# DRV8711EVM_FET.net
KiCad netlist of a schematic drawn in Altium Designer
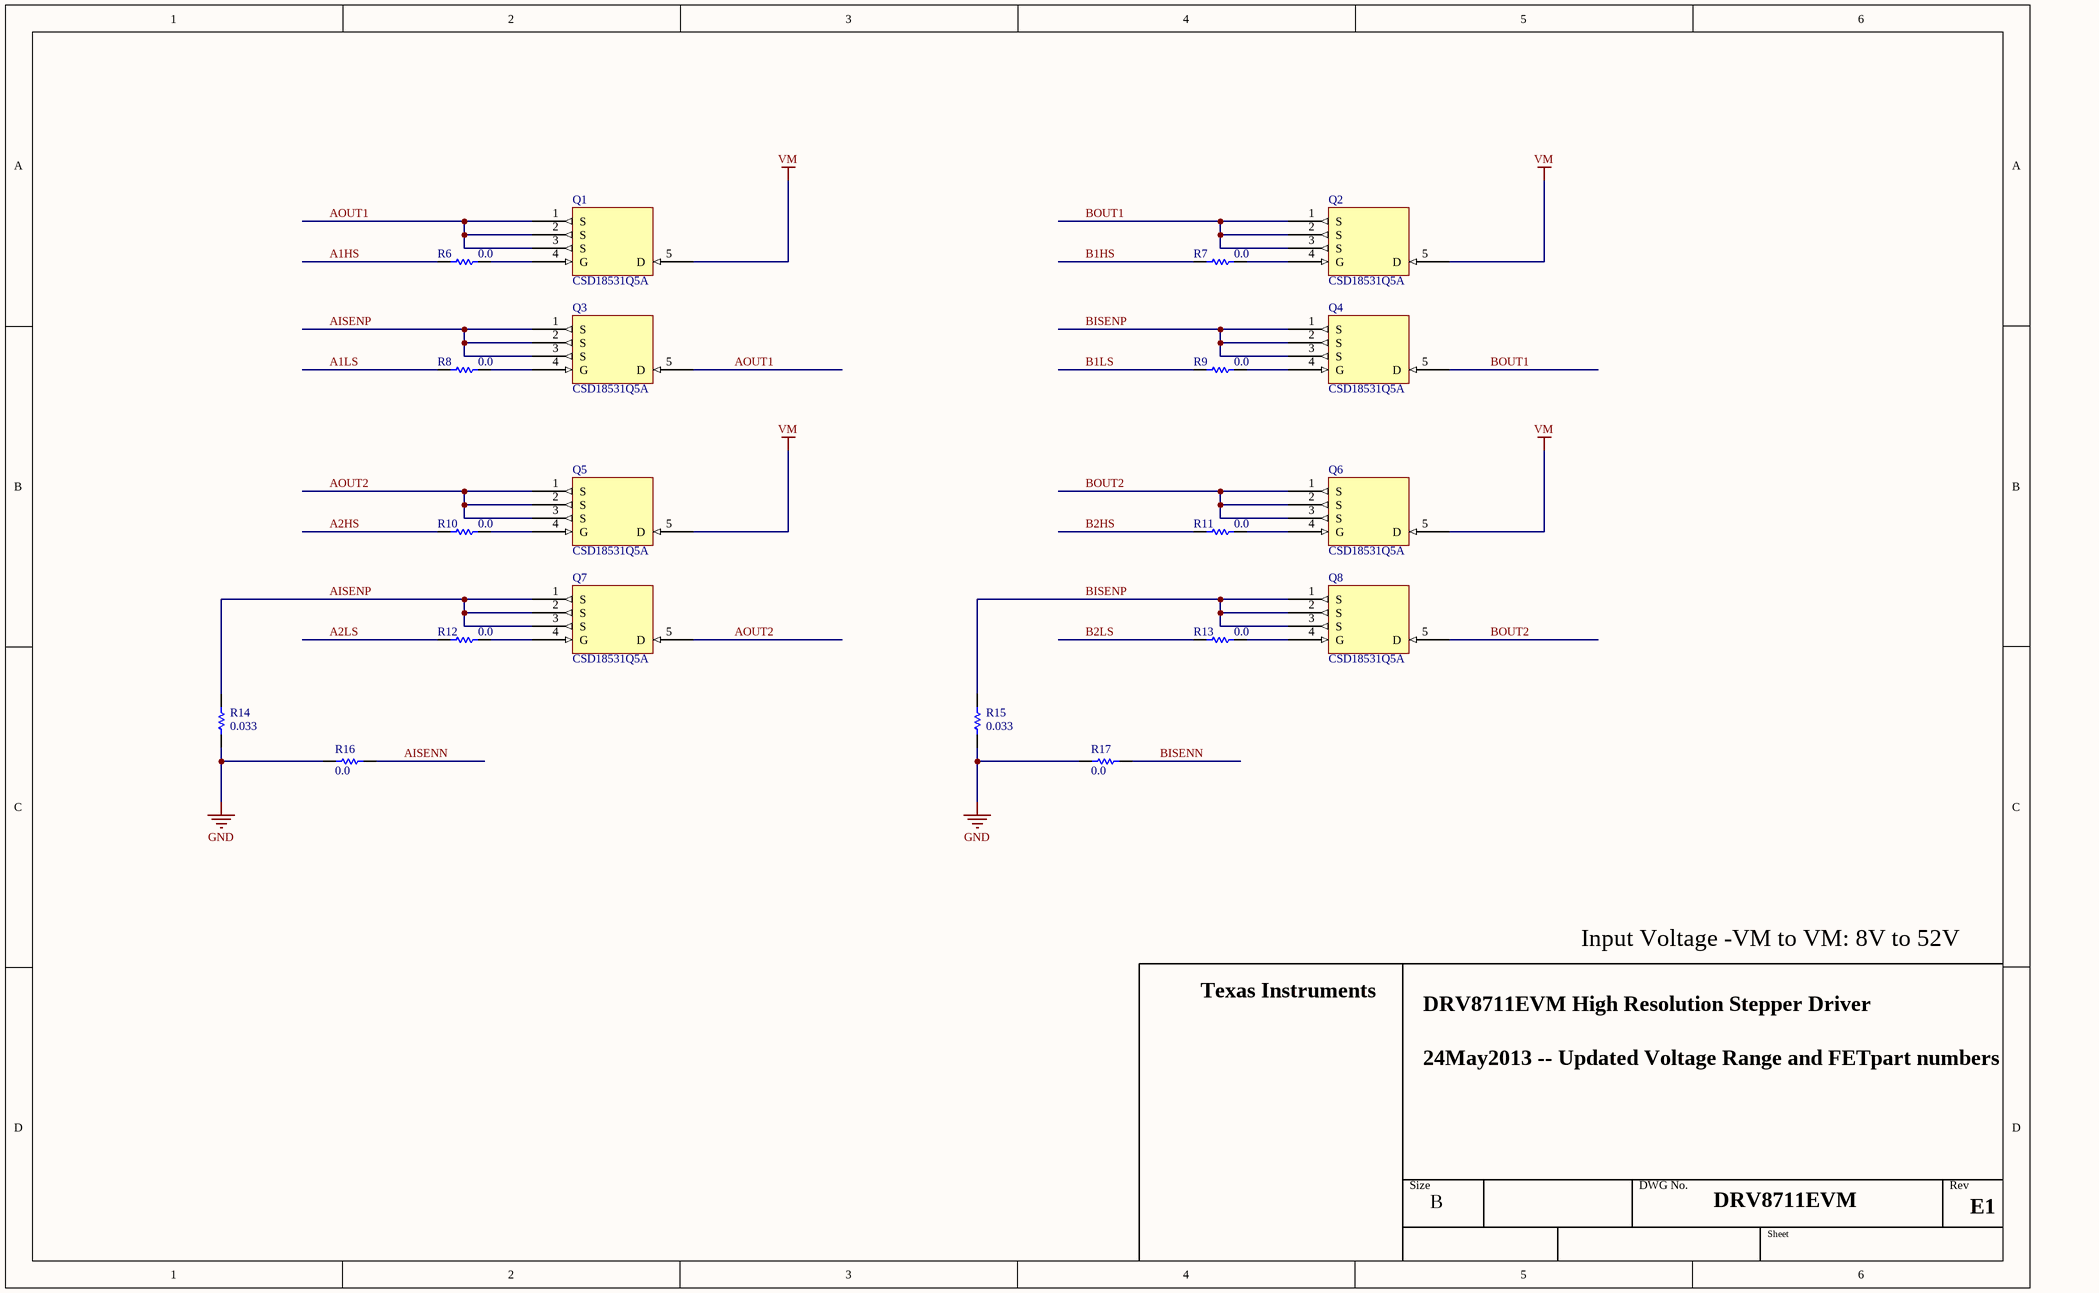
[diagram p0: DRV8711EVM_FET.SchDoc]

(export (version "E")
  (design (tool "Eeschema 10.0.6"))
  (components
    (comp (ref "Q1")
      (value "CSD18531Q5A")
      (description "MOSFET N-CH 60V 8SON")
      (fields (field (name "MANUFACTURER") "Texas Instruments"))
      (libsource (lib "JIQLIB") (part "IRLH5034"))
    )
    (comp (ref "Q2")
      (value "CSD18531Q5A")
      (description "MOSFET N-CH 60V 8SON")
      (fields (field (name "MANUFACTURER") "Texas Instruments"))
      (libsource (lib "JIQLIB") (part "IRLH5034"))
    )
    (comp (ref "Q3")
      (value "CSD18531Q5A")
      (description "MOSFET N-CH 60V 8SON")
      (fields (field (name "MANUFACTURER") "Texas Instruments"))
      (libsource (lib "JIQLIB") (part "IRLH5034"))
    )
    (comp (ref "Q4")
      (value "CSD18531Q5A")
      (description "MOSFET N-CH 60V 8SON")
      (fields (field (name "MANUFACTURER") "Texas Instruments"))
      (libsource (lib "JIQLIB") (part "IRLH5034"))
    )
    (comp (ref "Q5")
      (value "CSD18531Q5A")
      (description "MOSFET N-CH 60V 8SON")
      (fields (field (name "MANUFACTURER") "Texas Instruments"))
      (libsource (lib "JIQLIB") (part "IRLH5034"))
    )
    (comp (ref "Q6")
      (value "CSD18531Q5A")
      (description "MOSFET N-CH 60V 8SON")
      (fields (field (name "MANUFACTURER") "Texas Instruments"))
      (libsource (lib "JIQLIB") (part "IRLH5034"))
    )
    (comp (ref "Q7")
      (value "CSD18531Q5A")
      (description "MOSFET N-CH 60V 8SON")
      (fields (field (name "MANUFACTURER") "Texas Instruments"))
      (libsource (lib "JIQLIB") (part "IRLH5034"))
    )
    (comp (ref "Q8")
      (value "CSD18531Q5A")
      (description "MOSFET N-CH 60V 8SON")
      (fields (field (name "MANUFACTURER") "Texas Instruments"))
      (libsource (lib "JIQLIB") (part "IRLH5034"))
    )
    (comp (ref "R6")
      (value "0.0")
      (footprint "0603-SMT")
      (description "RES 0.0 OHM 1/10W 0603 SMD")
      (fields (field (name "MANUFACTURER") "Panasonic") (field (name "MFG PART NUMBER") "ERJ-3GEY0R00V"))
      (libsource (lib "Zerosen_Small") (part "Res1"))
    )
    (comp (ref "R7")
      (value "0.0")
      (footprint "0603-SMT")
      (description "RES 0.0 OHM 1/10W 0603 SMD")
      (fields (field (name "MANUFACTURER") "Panasonic") (field (name "MFG PART NUMBER") "ERJ-3GEY0R00V"))
      (libsource (lib "Zerosen_Small") (part "Res1"))
    )
    (comp (ref "R8")
      (value "0.0")
      (footprint "0603-SMT")
      (description "RES 0.0 OHM 1/10W 0603 SMD")
      (fields (field (name "MANUFACTURER") "Panasonic") (field (name "MFG PART NUMBER") "ERJ-3GEY0R00V"))
      (libsource (lib "Zerosen_Small") (part "Res1"))
    )
    (comp (ref "R9")
      (value "0.0")
      (footprint "0603-SMT")
      (description "RES 0.0 OHM 1/10W 0603 SMD")
      (fields (field (name "MANUFACTURER") "Panasonic") (field (name "MFG PART NUMBER") "ERJ-3GEY0R00V"))
      (libsource (lib "Zerosen_Small") (part "Res1"))
    )
    (comp (ref "R10")
      (value "0.0")
      (footprint "0603-SMT")
      (description "RES 0.0 OHM 1/10W 0603 SMD")
      (fields (field (name "MANUFACTURER") "Panasonic") (field (name "MFG PART NUMBER") "ERJ-3GEY0R00V"))
      (libsource (lib "Zerosen_Small") (part "Res1"))
    )
    (comp (ref "R11")
      (value "0.0")
      (footprint "0603-SMT")
      (description "RES 0.0 OHM 1/10W 0603 SMD")
      (fields (field (name "MANUFACTURER") "Panasonic") (field (name "MFG PART NUMBER") "ERJ-3GEY0R00V"))
      (libsource (lib "Zerosen_Small") (part "Res1"))
    )
    (comp (ref "R12")
      (value "0.0")
      (footprint "0603-SMT")
      (description "RES 0.0 OHM 1/10W 0603 SMD")
      (fields (field (name "MANUFACTURER") "Panasonic") (field (name "MFG PART NUMBER") "ERJ-3GEY0R00V"))
      (libsource (lib "Zerosen_Small") (part "Res1"))
    )
    (comp (ref "R13")
      (value "0.0")
      (footprint "0603-SMT")
      (description "RES 0.0 OHM 1/10W 0603 SMD")
      (fields (field (name "MANUFACTURER") "Panasonic") (field (name "MFG PART NUMBER") "ERJ-3GEY0R00V"))
      (libsource (lib "Zerosen_Small") (part "Res1"))
    )
    (comp (ref "R14")
      (value "0.033")
      (footprint "2818")
      (description "Resistor")
      (fields (field (name "MFG PART NUMBER") "WSH2818R0330FEA") (field (name "MANUFACTURER") "Vishay"))
      (libsource (lib "Miscellaneous Devices") (part "Res1"))
    )
    (comp (ref "R15")
      (value "0.033")
      (footprint "2818")
      (description "Resistor")
      (fields (field (name "MFG PART NUMBER") "WSH2818R0330FEA") (field (name "MANUFACTURER") "Vishay"))
      (libsource (lib "Miscellaneous Devices") (part "Res1"))
    )
    (comp (ref "R16")
      (value "0.0")
      (footprint "0603-SMT")
      (description "RES 0.0 OHM 1/10W 0603 SMD")
      (fields (field (name "MANUFACTURER") "Panasonic") (field (name "MFG PART NUMBER") "ERJ-3GEY0R00V"))
      (libsource (lib "Zerosen_Small") (part "Res1"))
    )
    (comp (ref "R17")
      (value "0.0")
      (footprint "0603-SMT")
      (description "RES 0.0 OHM 1/10W 0603 SMD")
      (fields (field (name "MANUFACTURER") "Panasonic") (field (name "MFG PART NUMBER") "ERJ-3GEY0R00V"))
      (libsource (lib "Zerosen_Small") (part "Res1"))
    )
  )
  (nets
    (net (code "1") (name "/A1HS") (class "Default")
      (node (ref "R6") (pin "1") (pinfunction "1_1") (pintype "passive"))
    )
    (net (code "2") (name "/A1LS") (class "Default")
      (node (ref "R8") (pin "1") (pinfunction "1_1") (pintype "passive"))
    )
    (net (code "3") (name "/A2HS") (class "Default")
      (node (ref "R10") (pin "1") (pinfunction "1_1") (pintype "passive"))
    )
    (net (code "4") (name "/A2LS") (class "Default")
      (node (ref "R12") (pin "1") (pinfunction "1_1") (pintype "passive"))
    )
    (net (code "5") (name "/AISENN") (class "Default")
      (node (ref "R16") (pin "1") (pinfunction "1_1") (pintype "passive"))
    )
    (net (code "6") (name "/AISENP") (class "Default")
      (node (ref "Q3") (pin "1") (pinfunction "S_1") (pintype "output"))
      (node (ref "Q3") (pin "2") (pinfunction "S_2") (pintype "output"))
      (node (ref "Q3") (pin "3") (pinfunction "S_3") (pintype "output"))
      (node (ref "Q7") (pin "1") (pinfunction "S_1") (pintype "output"))
      (node (ref "Q7") (pin "2") (pinfunction "S_2") (pintype "output"))
      (node (ref "Q7") (pin "3") (pinfunction "S_3") (pintype "output"))
      (node (ref "R14") (pin "2") (pinfunction "2_2") (pintype "passive"))
    )
    (net (code "7") (name "/AOUT1") (class "Default")
      (node (ref "Q1") (pin "1") (pinfunction "S_1") (pintype "output"))
      (node (ref "Q1") (pin "2") (pinfunction "S_2") (pintype "output"))
      (node (ref "Q1") (pin "3") (pinfunction "S_3") (pintype "output"))
      (node (ref "Q3") (pin "5") (pinfunction "D_5") (pintype "input"))
    )
    (net (code "8") (name "/AOUT2") (class "Default")
      (node (ref "Q5") (pin "1") (pinfunction "S_1") (pintype "output"))
      (node (ref "Q5") (pin "2") (pinfunction "S_2") (pintype "output"))
      (node (ref "Q5") (pin "3") (pinfunction "S_3") (pintype "output"))
      (node (ref "Q7") (pin "5") (pinfunction "D_5") (pintype "input"))
    )
    (net (code "9") (name "/B1HS") (class "Default")
      (node (ref "R7") (pin "1") (pinfunction "1_1") (pintype "passive"))
    )
    (net (code "10") (name "/B1LS") (class "Default")
      (node (ref "R9") (pin "1") (pinfunction "1_1") (pintype "passive"))
    )
    (net (code "11") (name "/B2HS") (class "Default")
      (node (ref "R11") (pin "1") (pinfunction "1_1") (pintype "passive"))
    )
    (net (code "12") (name "/B2LS") (class "Default")
      (node (ref "R13") (pin "1") (pinfunction "1_1") (pintype "passive"))
    )
    (net (code "13") (name "/BISENN") (class "Default")
      (node (ref "R17") (pin "1") (pinfunction "1_1") (pintype "passive"))
    )
    (net (code "14") (name "/BISENP") (class "Default")
      (node (ref "Q4") (pin "1") (pinfunction "S_1") (pintype "output"))
      (node (ref "Q4") (pin "2") (pinfunction "S_2") (pintype "output"))
      (node (ref "Q4") (pin "3") (pinfunction "S_3") (pintype "output"))
      (node (ref "Q8") (pin "1") (pinfunction "S_1") (pintype "output"))
      (node (ref "Q8") (pin "2") (pinfunction "S_2") (pintype "output"))
      (node (ref "Q8") (pin "3") (pinfunction "S_3") (pintype "output"))
      (node (ref "R15") (pin "2") (pinfunction "2_2") (pintype "passive"))
    )
    (net (code "15") (name "/BOUT1") (class "Default")
      (node (ref "Q2") (pin "1") (pinfunction "S_1") (pintype "output"))
      (node (ref "Q2") (pin "2") (pinfunction "S_2") (pintype "output"))
      (node (ref "Q2") (pin "3") (pinfunction "S_3") (pintype "output"))
      (node (ref "Q4") (pin "5") (pinfunction "D_5") (pintype "input"))
    )
    (net (code "16") (name "/BOUT2") (class "Default")
      (node (ref "Q6") (pin "1") (pinfunction "S_1") (pintype "output"))
      (node (ref "Q6") (pin "2") (pinfunction "S_2") (pintype "output"))
      (node (ref "Q6") (pin "3") (pinfunction "S_3") (pintype "output"))
      (node (ref "Q8") (pin "5") (pinfunction "D_5") (pintype "input"))
    )
    (net (code "17") (name "GND") (class "Default")
      (node (ref "R14") (pin "1") (pinfunction "1_1") (pintype "passive"))
      (node (ref "R15") (pin "1") (pinfunction "1_1") (pintype "passive"))
      (node (ref "R16") (pin "2") (pinfunction "2_2") (pintype "passive"))
      (node (ref "R17") (pin "2") (pinfunction "2_2") (pintype "passive"))
    )
    (net (code "18") (name "Net-(Q1-G)") (class "Default")
      (node (ref "Q1") (pin "4") (pinfunction "G_4") (pintype "input"))
      (node (ref "R6") (pin "2") (pinfunction "2_2") (pintype "passive"))
    )
    (net (code "19") (name "Net-(Q2-G)") (class "Default")
      (node (ref "Q2") (pin "4") (pinfunction "G_4") (pintype "input"))
      (node (ref "R7") (pin "2") (pinfunction "2_2") (pintype "passive"))
    )
    (net (code "20") (name "Net-(Q3-G)") (class "Default")
      (node (ref "Q3") (pin "4") (pinfunction "G_4") (pintype "input"))
      (node (ref "R8") (pin "2") (pinfunction "2_2") (pintype "passive"))
    )
    (net (code "21") (name "Net-(Q4-G)") (class "Default")
      (node (ref "Q4") (pin "4") (pinfunction "G_4") (pintype "input"))
      (node (ref "R9") (pin "2") (pinfunction "2_2") (pintype "passive"))
    )
    (net (code "22") (name "Net-(Q5-G)") (class "Default")
      (node (ref "Q5") (pin "4") (pinfunction "G_4") (pintype "input"))
      (node (ref "R10") (pin "2") (pinfunction "2_2") (pintype "passive"))
    )
    (net (code "23") (name "Net-(Q6-G)") (class "Default")
      (node (ref "Q6") (pin "4") (pinfunction "G_4") (pintype "input"))
      (node (ref "R11") (pin "2") (pinfunction "2_2") (pintype "passive"))
    )
    (net (code "24") (name "Net-(Q7-G)") (class "Default")
      (node (ref "Q7") (pin "4") (pinfunction "G_4") (pintype "input"))
      (node (ref "R12") (pin "2") (pinfunction "2_2") (pintype "passive"))
    )
    (net (code "25") (name "Net-(Q8-G)") (class "Default")
      (node (ref "Q8") (pin "4") (pinfunction "G_4") (pintype "input"))
      (node (ref "R13") (pin "2") (pinfunction "2_2") (pintype "passive"))
    )
    (net (code "26") (name "VM") (class "Default")
      (node (ref "Q1") (pin "5") (pinfunction "D_5") (pintype "input"))
      (node (ref "Q2") (pin "5") (pinfunction "D_5") (pintype "input"))
      (node (ref "Q5") (pin "5") (pinfunction "D_5") (pintype "input"))
      (node (ref "Q6") (pin "5") (pinfunction "D_5") (pintype "input"))
    )
  )
)
